# LAN8870_PINOUT.net
KiCad netlist of a schematic drawn in Altium Designer
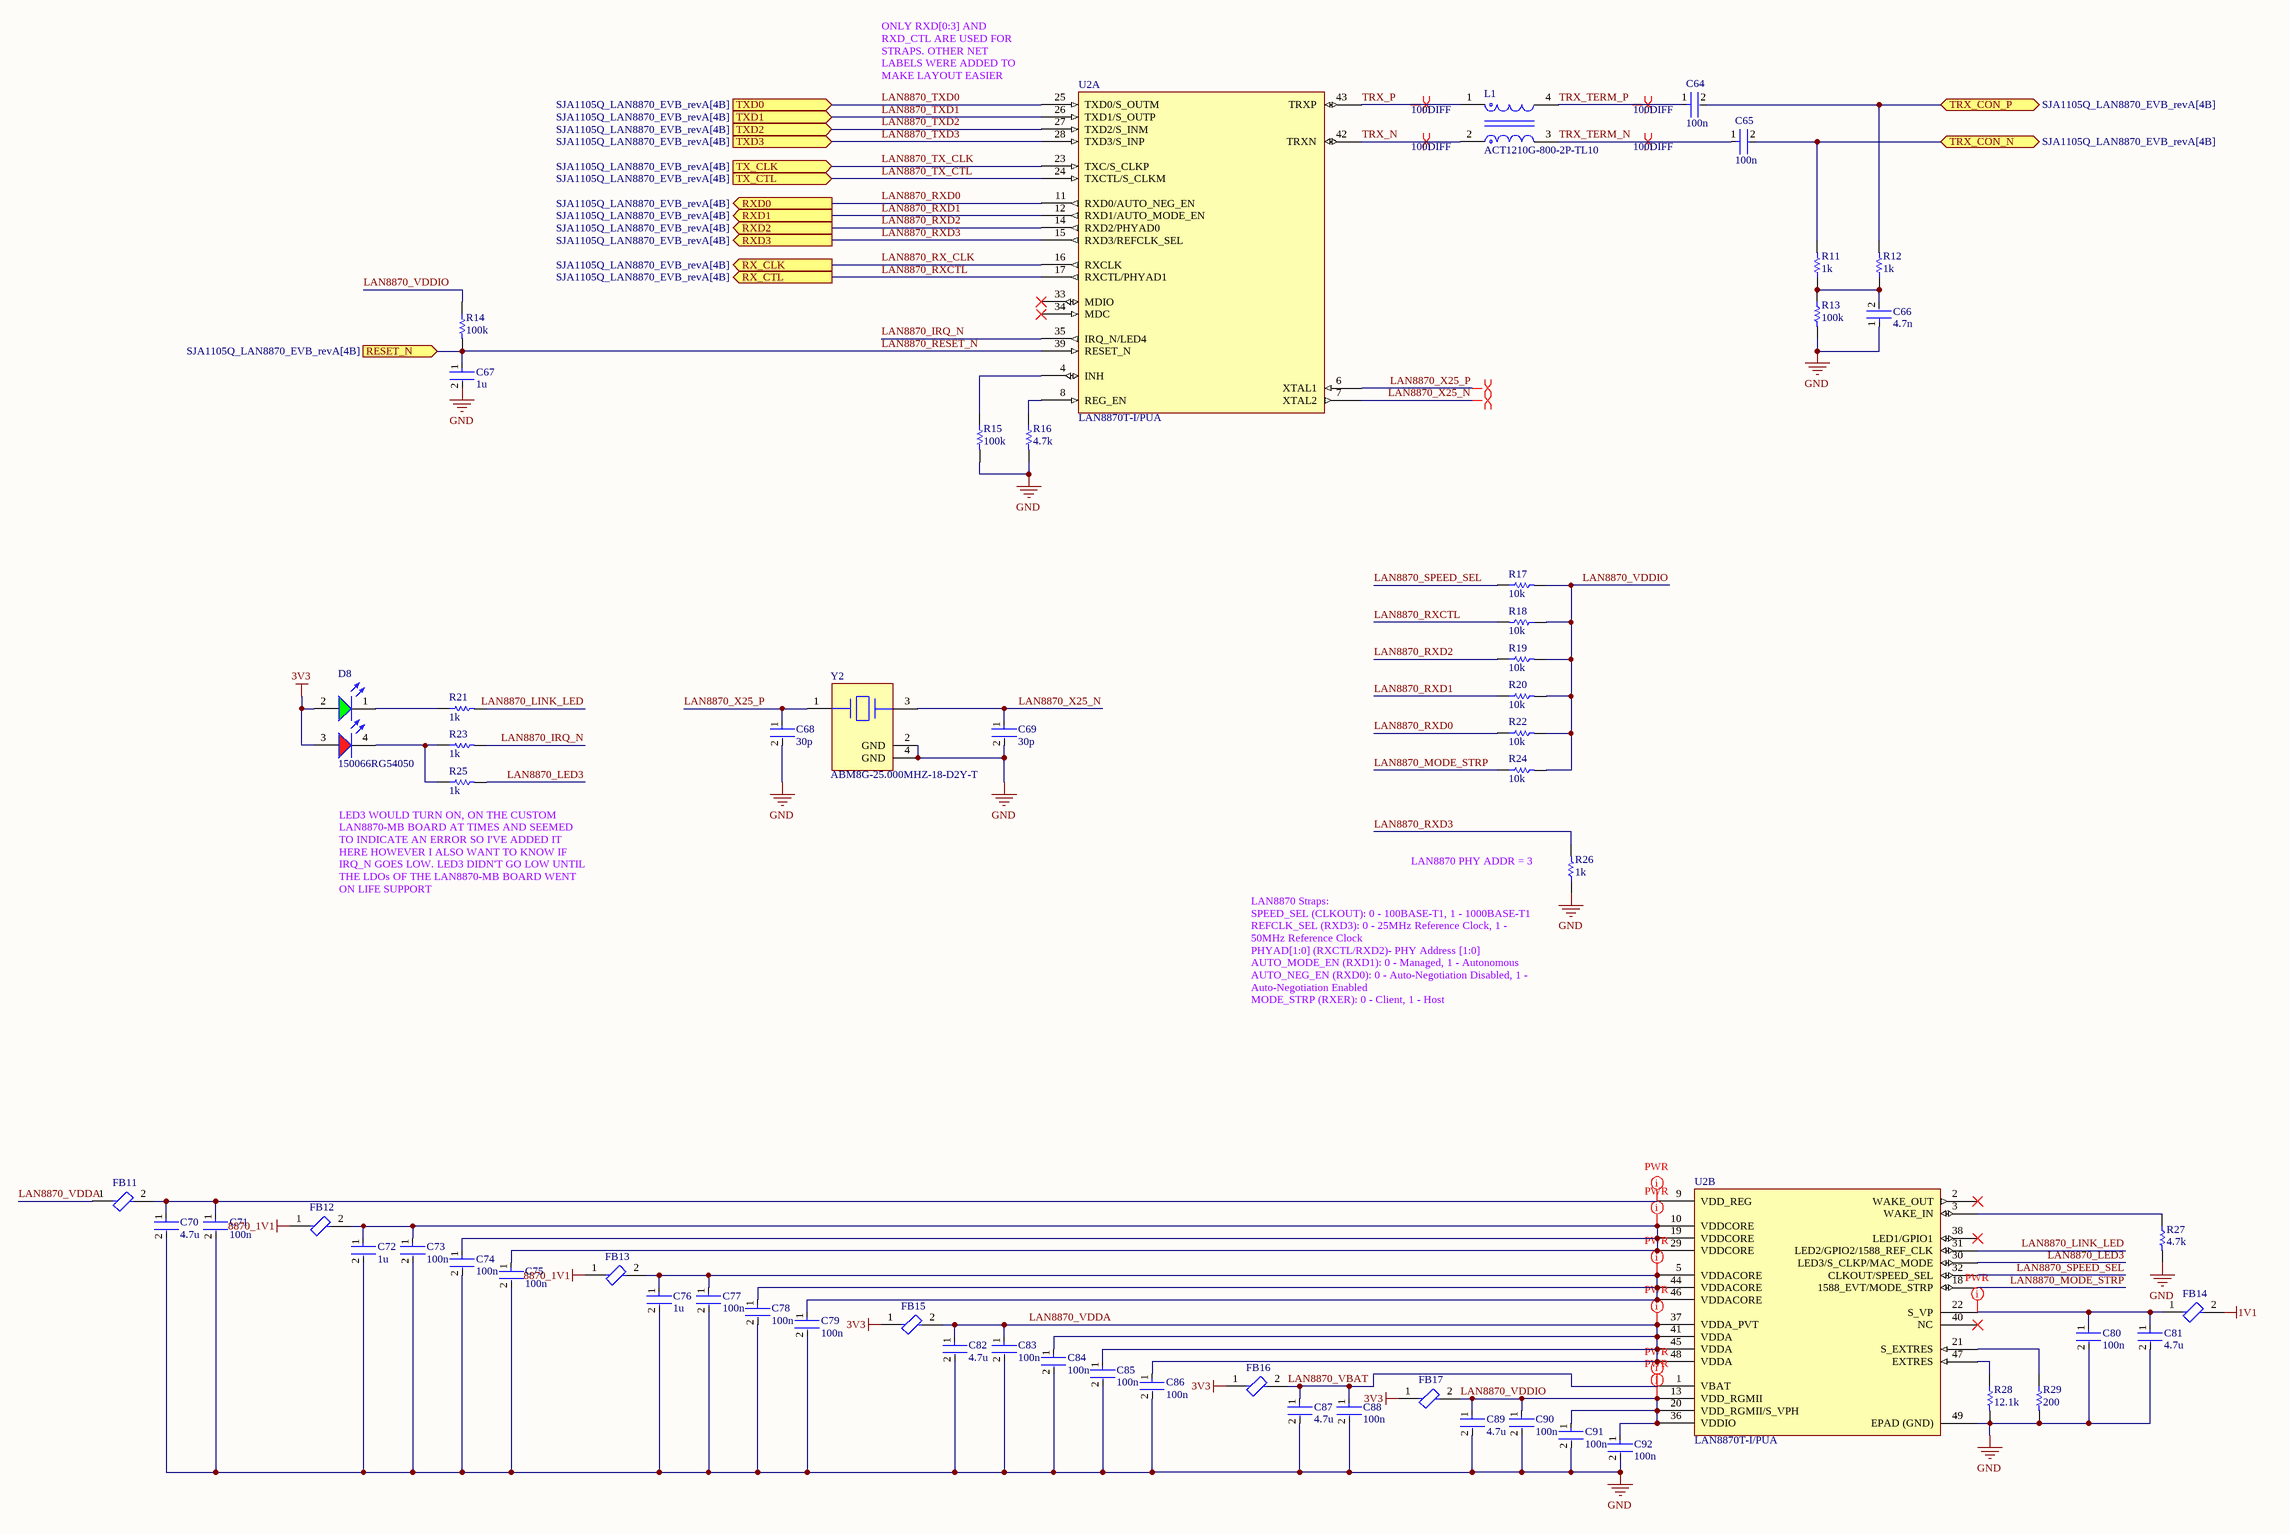
[diagram p0: LAN8870_PINOUT.SchDoc]

(export (version "E")
  (design (tool "Eeschema 10.0.6"))
  (components
    (comp (ref "C64")
      (value "100n")
      (footprint "FP-0402-L_1_0_0_05-W_0_5-IPC_A")
      (description "LARGE PADS, 0402 CAP, CHANGE COMMENT TO MATCH REAL P/N")
      (libsource (lib "Space Concordia") (part "b4654b650e69147ec39a6b967a45e02"))
    )
    (comp (ref "C65")
      (value "100n")
      (footprint "FP-0402-L_1_0_0_05-W_0_5-IPC_A")
      (description "LARGE PADS, 0402 CAP, CHANGE COMMENT TO MATCH REAL P/N")
      (libsource (lib "Space Concordia") (part "b4654b650e69147ec39a6b967a45e02"))
    )
    (comp (ref "C66")
      (value "4.7n")
      (footprint "FP-0402-L_1_0_0_05-W_0_5-IPC_A")
      (description "LARGE PADS, 0402 CAP, CHANGE COMMENT TO MATCH REAL P/N")
      (libsource (lib "Space Concordia") (part "b4654b650e69147ec39a6b967a45e02"))
    )
    (comp (ref "C67")
      (value "1u")
      (footprint "FP-0402-L_1_0_0_05-W_0_5-IPC_A")
      (description "LARGE PADS, 0402 CAP, CHANGE COMMENT TO MATCH REAL P/N")
      (libsource (lib "Space Concordia") (part "b4654b650e69147ec39a6b967a45e02"))
    )
    (comp (ref "C68")
      (value "30p")
      (footprint "FP-0402-L_1_0_0_05-W_0_5-IPC_A")
      (description "LARGE PADS, 0402 CAP, CHANGE COMMENT TO MATCH REAL P/N")
      (libsource (lib "Space Concordia") (part "b4654b650e69147ec39a6b967a45e02"))
    )
    (comp (ref "C69")
      (value "30p")
      (footprint "FP-0402-L_1_0_0_05-W_0_5-IPC_A")
      (description "LARGE PADS, 0402 CAP, CHANGE COMMENT TO MATCH REAL P/N")
      (libsource (lib "Space Concordia") (part "b4654b650e69147ec39a6b967a45e02"))
    )
    (comp (ref "C70")
      (value "4.7u")
      (footprint "FP-0402-L_1_0_0_05-W_0_5-IPC_A")
      (description "LARGE PADS, 0402 CAP, CHANGE COMMENT TO MATCH REAL P/N")
      (libsource (lib "Space Concordia") (part "b4654b650e69147ec39a6b967a45e02"))
    )
    (comp (ref "C71")
      (value "100n")
      (footprint "FP-0402-L_1_0_0_05-W_0_5-IPC_A")
      (description "LARGE PADS, 0402 CAP, CHANGE COMMENT TO MATCH REAL P/N")
      (libsource (lib "Space Concordia") (part "b4654b650e69147ec39a6b967a45e02"))
    )
    (comp (ref "C72")
      (value "1u")
      (footprint "FP-0402-L_1_0_0_05-W_0_5-IPC_A")
      (description "LARGE PADS, 0402 CAP, CHANGE COMMENT TO MATCH REAL P/N")
      (libsource (lib "Space Concordia") (part "b4654b650e69147ec39a6b967a45e02"))
    )
    (comp (ref "C73")
      (value "100n")
      (footprint "FP-0402-L_1_0_0_05-W_0_5-IPC_A")
      (description "LARGE PADS, 0402 CAP, CHANGE COMMENT TO MATCH REAL P/N")
      (libsource (lib "Space Concordia") (part "b4654b650e69147ec39a6b967a45e02"))
    )
    (comp (ref "C74")
      (value "100n")
      (footprint "FP-0402-L_1_0_0_05-W_0_5-IPC_A")
      (description "LARGE PADS, 0402 CAP, CHANGE COMMENT TO MATCH REAL P/N")
      (libsource (lib "Space Concordia") (part "b4654b650e69147ec39a6b967a45e02"))
    )
    (comp (ref "C75")
      (value "100n")
      (footprint "FP-0402-L_1_0_0_05-W_0_5-IPC_A")
      (description "LARGE PADS, 0402 CAP, CHANGE COMMENT TO MATCH REAL P/N")
      (libsource (lib "Space Concordia") (part "b4654b650e69147ec39a6b967a45e02"))
    )
    (comp (ref "C76")
      (value "1u")
      (footprint "FP-0402-L_1_0_0_05-W_0_5-IPC_A")
      (description "LARGE PADS, 0402 CAP, CHANGE COMMENT TO MATCH REAL P/N")
      (libsource (lib "Space Concordia") (part "b4654b650e69147ec39a6b967a45e02"))
    )
    (comp (ref "C77")
      (value "100n")
      (footprint "FP-0402-L_1_0_0_05-W_0_5-IPC_A")
      (description "LARGE PADS, 0402 CAP, CHANGE COMMENT TO MATCH REAL P/N")
      (libsource (lib "Space Concordia") (part "b4654b650e69147ec39a6b967a45e02"))
    )
    (comp (ref "C78")
      (value "100n")
      (footprint "FP-0402-L_1_0_0_05-W_0_5-IPC_A")
      (description "LARGE PADS, 0402 CAP, CHANGE COMMENT TO MATCH REAL P/N")
      (libsource (lib "Space Concordia") (part "b4654b650e69147ec39a6b967a45e02"))
    )
    (comp (ref "C79")
      (value "100n")
      (footprint "FP-0402-L_1_0_0_05-W_0_5-IPC_A")
      (description "LARGE PADS, 0402 CAP, CHANGE COMMENT TO MATCH REAL P/N")
      (libsource (lib "Space Concordia") (part "b4654b650e69147ec39a6b967a45e02"))
    )
    (comp (ref "C80")
      (value "100n")
      (footprint "FP-0402-L_1_0_0_05-W_0_5-IPC_A")
      (description "LARGE PADS, 0402 CAP, CHANGE COMMENT TO MATCH REAL P/N")
      (libsource (lib "Space Concordia") (part "b4654b650e69147ec39a6b967a45e02"))
    )
    (comp (ref "C81")
      (value "4.7u")
      (footprint "FP-0402-L_1_0_0_05-W_0_5-IPC_A")
      (description "LARGE PADS, 0402 CAP, CHANGE COMMENT TO MATCH REAL P/N")
      (libsource (lib "Space Concordia") (part "b4654b650e69147ec39a6b967a45e02"))
    )
    (comp (ref "C82")
      (value "4.7u")
      (footprint "FP-0402-L_1_0_0_05-W_0_5-IPC_A")
      (description "LARGE PADS, 0402 CAP, CHANGE COMMENT TO MATCH REAL P/N")
      (libsource (lib "Space Concordia") (part "b4654b650e69147ec39a6b967a45e02"))
    )
    (comp (ref "C83")
      (value "100n")
      (footprint "FP-0402-L_1_0_0_05-W_0_5-IPC_A")
      (description "LARGE PADS, 0402 CAP, CHANGE COMMENT TO MATCH REAL P/N")
      (libsource (lib "Space Concordia") (part "b4654b650e69147ec39a6b967a45e02"))
    )
    (comp (ref "C84")
      (value "100n")
      (footprint "FP-0402-L_1_0_0_05-W_0_5-IPC_A")
      (description "LARGE PADS, 0402 CAP, CHANGE COMMENT TO MATCH REAL P/N")
      (libsource (lib "Space Concordia") (part "b4654b650e69147ec39a6b967a45e02"))
    )
    (comp (ref "C85")
      (value "100n")
      (footprint "FP-0402-L_1_0_0_05-W_0_5-IPC_A")
      (description "LARGE PADS, 0402 CAP, CHANGE COMMENT TO MATCH REAL P/N")
      (libsource (lib "Space Concordia") (part "b4654b650e69147ec39a6b967a45e02"))
    )
    (comp (ref "C86")
      (value "100n")
      (footprint "FP-0402-L_1_0_0_05-W_0_5-IPC_A")
      (description "LARGE PADS, 0402 CAP, CHANGE COMMENT TO MATCH REAL P/N")
      (libsource (lib "Space Concordia") (part "b4654b650e69147ec39a6b967a45e02"))
    )
    (comp (ref "C87")
      (value "4.7u")
      (footprint "FP-0402-L_1_0_0_05-W_0_5-IPC_A")
      (description "LARGE PADS, 0402 CAP, CHANGE COMMENT TO MATCH REAL P/N")
      (libsource (lib "Space Concordia") (part "b4654b650e69147ec39a6b967a45e02"))
    )
    (comp (ref "C88")
      (value "100n")
      (footprint "FP-0402-L_1_0_0_05-W_0_5-IPC_A")
      (description "LARGE PADS, 0402 CAP, CHANGE COMMENT TO MATCH REAL P/N")
      (libsource (lib "Space Concordia") (part "b4654b650e69147ec39a6b967a45e02"))
    )
    (comp (ref "C89")
      (value "4.7u")
      (footprint "FP-0402-L_1_0_0_05-W_0_5-IPC_A")
      (description "LARGE PADS, 0402 CAP, CHANGE COMMENT TO MATCH REAL P/N")
      (libsource (lib "Space Concordia") (part "b4654b650e69147ec39a6b967a45e02"))
    )
    (comp (ref "C90")
      (value "100n")
      (footprint "FP-0402-L_1_0_0_05-W_0_5-IPC_A")
      (description "LARGE PADS, 0402 CAP, CHANGE COMMENT TO MATCH REAL P/N")
      (libsource (lib "Space Concordia") (part "b4654b650e69147ec39a6b967a45e02"))
    )
    (comp (ref "C91")
      (value "100n")
      (footprint "FP-0402-L_1_0_0_05-W_0_5-IPC_A")
      (description "LARGE PADS, 0402 CAP, CHANGE COMMENT TO MATCH REAL P/N")
      (libsource (lib "Space Concordia") (part "b4654b650e69147ec39a6b967a45e02"))
    )
    (comp (ref "C92")
      (value "100n")
      (footprint "FP-0402-L_1_0_0_05-W_0_5-IPC_A")
      (description "LARGE PADS, 0402 CAP, CHANGE COMMENT TO MATCH REAL P/N")
      (libsource (lib "Space Concordia") (part "b4654b650e69147ec39a6b967a45e02"))
    )
    (comp (ref "D8")
      (value "150066RG54050")
      (footprint "WL-SBCD_0606")
      (description "Led, Red/Grn, 180Mcd/230Mcd, 624Nm/525Nm Rohs Compliant: Yes")
      (fields (field (name "SOURCE") "rgled.SchLib"))
      (libsource (lib "Space Concordia") (part "CMP-004-00034-2"))
    )
    (comp (ref "FB11")
      (value "BLM18KG331SH1D")
      (footprint "FP-BLM18-0_15-t0_8-IPC_B")
      (description "Chip Ferrite Bead, 0603, 330Ω @ 100MHz, 0.08Ω, 25%, 1.7A")
      (libsource (lib "Altium Content Vault") (part "5f30dd21d616792df468990f7003faa"))
    )
    (comp (ref "FB12")
      (value "BLM18KG331SH1D")
      (footprint "FP-BLM18-0_15-t0_8-IPC_B")
      (description "Chip Ferrite Bead, 0603, 330Ω @ 100MHz, 0.08Ω, 25%, 1.7A")
      (libsource (lib "Altium Content Vault") (part "5f30dd21d616792df468990f7003faa"))
    )
    (comp (ref "FB13")
      (value "BLM18KG331SH1D")
      (footprint "FP-BLM18-0_15-t0_8-IPC_B")
      (description "Chip Ferrite Bead, 0603, 330Ω @ 100MHz, 0.08Ω, 25%, 1.7A")
      (libsource (lib "Altium Content Vault") (part "5f30dd21d616792df468990f7003faa"))
    )
    (comp (ref "FB14")
      (value "BLM18KG331SH1D")
      (footprint "FP-BLM18-0_15-t0_8-IPC_B")
      (description "Chip Ferrite Bead, 0603, 330Ω @ 100MHz, 0.08Ω, 25%, 1.7A")
      (libsource (lib "Altium Content Vault") (part "5f30dd21d616792df468990f7003faa"))
    )
    (comp (ref "FB15")
      (value "BLM18KG331SH1D")
      (footprint "FP-BLM18-0_15-t0_8-IPC_B")
      (description "Chip Ferrite Bead, 0603, 330Ω @ 100MHz, 0.08Ω, 25%, 1.7A")
      (libsource (lib "Altium Content Vault") (part "5f30dd21d616792df468990f7003faa"))
    )
    (comp (ref "FB16")
      (value "BLM18KG331SH1D")
      (footprint "FP-BLM18-0_15-t0_8-IPC_B")
      (description "Chip Ferrite Bead, 0603, 330Ω @ 100MHz, 0.08Ω, 25%, 1.7A")
      (libsource (lib "Altium Content Vault") (part "5f30dd21d616792df468990f7003faa"))
    )
    (comp (ref "FB17")
      (value "BLM18KG331SH1D")
      (footprint "FP-BLM18-0_15-t0_8-IPC_B")
      (description "Chip Ferrite Bead, 0603, 330Ω @ 100MHz, 0.08Ω, 25%, 1.7A")
      (libsource (lib "Altium Content Vault") (part "5f30dd21d616792df468990f7003faa"))
    )
    (comp (ref "L1")
      (value "ACT1210G-800-2P-TL10")
      (footprint "FP-ACT1210G-800-2P-TL10-MFG")
      (description "CMC 80UH 70MA 2LN 3.8KOHM SMD")
      (libsource (lib "Altium Content Vault") (part "b4b74a627ea9af473eaab86227aab92"))
    )
    (comp (ref "R11")
      (value "1k")
      (footprint "R0603B")
      (description "Resistor")
      (libsource (lib "Space Concordia") (part "Resistor"))
    )
    (comp (ref "R12")
      (value "1k")
      (footprint "R0603B")
      (description "Resistor")
      (libsource (lib "Space Concordia") (part "Resistor"))
    )
    (comp (ref "R13")
      (value "100k")
      (footprint "R0603B")
      (description "Resistor")
      (libsource (lib "Space Concordia") (part "Resistor"))
    )
    (comp (ref "R14")
      (value "100k")
      (footprint "R0603B")
      (description "Resistor")
      (libsource (lib "Space Concordia") (part "Resistor"))
    )
    (comp (ref "R15")
      (value "100k")
      (footprint "R0603B")
      (description "Resistor")
      (libsource (lib "Space Concordia") (part "Resistor"))
    )
    (comp (ref "R16")
      (value "4.7k")
      (footprint "R0603B")
      (description "Resistor")
      (libsource (lib "Space Concordia") (part "Resistor"))
    )
    (comp (ref "R17")
      (value "10k")
      (footprint "R0603B")
      (description "Resistor")
      (libsource (lib "Space Concordia") (part "Resistor"))
    )
    (comp (ref "R18")
      (value "10k")
      (footprint "R0603B")
      (description "Resistor")
      (libsource (lib "Space Concordia") (part "Resistor"))
    )
    (comp (ref "R19")
      (value "10k")
      (footprint "R0603B")
      (description "Resistor")
      (libsource (lib "Space Concordia") (part "Resistor"))
    )
    (comp (ref "R20")
      (value "10k")
      (footprint "R0603B")
      (description "Resistor")
      (libsource (lib "Space Concordia") (part "Resistor"))
    )
    (comp (ref "R21")
      (value "1k")
      (footprint "R0603B")
      (description "Resistor")
      (libsource (lib "Space Concordia") (part "Resistor"))
    )
    (comp (ref "R22")
      (value "10k")
      (footprint "R0603B")
      (description "Resistor")
      (libsource (lib "Space Concordia") (part "Resistor"))
    )
    (comp (ref "R23")
      (value "1k")
      (footprint "R0603B")
      (description "Resistor")
      (libsource (lib "Space Concordia") (part "Resistor"))
    )
    (comp (ref "R24")
      (value "10k")
      (footprint "R0603B")
      (description "Resistor")
      (libsource (lib "Space Concordia") (part "Resistor"))
    )
    (comp (ref "R25")
      (value "1k")
      (footprint "R0603B")
      (description "Resistor")
      (libsource (lib "Space Concordia") (part "Resistor"))
    )
    (comp (ref "R26")
      (value "1k")
      (footprint "R0603B")
      (description "Resistor")
      (libsource (lib "Space Concordia") (part "Resistor"))
    )
    (comp (ref "R27")
      (value "4.7k")
      (footprint "R0603B")
      (description "Resistor")
      (libsource (lib "Space Concordia") (part "Resistor"))
    )
    (comp (ref "R28")
      (value "12.1k")
      (footprint "R0603B")
      (description "Resistor")
      (libsource (lib "Space Concordia") (part "Resistor"))
    )
    (comp (ref "R29")
      (value "200")
      (footprint "R0603B")
      (description "Resistor")
      (libsource (lib "Space Concordia") (part "Resistor"))
    )
    (comp (ref "U2")
      (value "LAN8870T-I/PUA")
      (footprint "QFN50P700X700X100_HS-49N")
      (description "100/1000BASE-T1 Rgmii/sgmii Phy")
      (libsource (lib "Space Concordia") (part "LAN8870T-I_PUA"))
    )
    (comp (ref "Y2")
      (value "ABM8G-25.000MHZ-18-D2Y-T")
      (footprint "FP-ABM8G-MFG")
      (description "Crystal 25MHz ±20ppm (Tol) ±30ppm (Stability) 18pF FUND 60Ω 4-Pin SMD T/R")
      (fields (field (name "TOLERANCE") "20ppm"))
      (libsource (lib "Altium Content Vault") (part "48e526d86b7f2615d98721063c72f49"))
    )
  )
  (nets
    (net (code "1") (name "/LAN8870_IRQ_N") (class "Default")
      (node (ref "R23") (pin "2") (pinfunction "2_2") (pintype "passive"))
      (node (ref "U2") (pin "35") (pinfunction "IRQ_N/LED4_35") (pintype "output"))
    )
    (net (code "2") (name "/LAN8870_LED3") (class "Default")
      (node (ref "R25") (pin "2") (pinfunction "2_2") (pintype "passive"))
      (node (ref "U2") (pin "30") (pinfunction "LED3/S_CLKP/MAC_MODE_30") (pintype "bidirectional"))
    )
    (net (code "3") (name "/LAN8870_LINK_LED") (class "Default")
      (node (ref "R21") (pin "2") (pinfunction "2_2") (pintype "passive"))
      (node (ref "U2") (pin "31") (pinfunction "LED2/GPIO2/1588_REF_CLK_31") (pintype "bidirectional"))
    )
    (net (code "4") (name "/LAN8870_MODE_STRP") (class "Default")
      (node (ref "R24") (pin "1") (pinfunction "1_1") (pintype "passive"))
      (node (ref "U2") (pin "18") (pinfunction "1588_EVT/MODE_STRP_18") (pintype "bidirectional"))
    )
    (net (code "5") (name "/LAN8870_RESET_N") (class "Default")
      (node (ref "C67") (pin "1") (pinfunction "1_1") (pintype "passive"))
      (node (ref "R14") (pin "2") (pinfunction "2_2") (pintype "passive"))
      (node (ref "U2") (pin "39") (pinfunction "RESET_N_39") (pintype "input"))
    )
    (net (code "6") (name "/LAN8870_RXCTL") (class "Default")
      (node (ref "R18") (pin "2") (pinfunction "2_2") (pintype "passive"))
      (node (ref "U2") (pin "17") (pinfunction "RXCTL/PHYAD1_17") (pintype "output"))
    )
    (net (code "7") (name "/LAN8870_RXD0") (class "Default")
      (node (ref "R22") (pin "1") (pinfunction "1_1") (pintype "passive"))
      (node (ref "U2") (pin "11") (pinfunction "RXD0/AUTO_NEG_EN_11") (pintype "output"))
    )
    (net (code "8") (name "/LAN8870_RXD1") (class "Default")
      (node (ref "R20") (pin "1") (pinfunction "1_1") (pintype "passive"))
      (node (ref "U2") (pin "12") (pinfunction "RXD1/AUTO_MODE_EN_12") (pintype "output"))
    )
    (net (code "9") (name "/LAN8870_RXD2") (class "Default")
      (node (ref "R19") (pin "1") (pinfunction "1_1") (pintype "passive"))
      (node (ref "U2") (pin "14") (pinfunction "RXD2/PHYAD0_14") (pintype "output"))
    )
    (net (code "10") (name "/LAN8870_RXD3") (class "Default")
      (node (ref "R26") (pin "2") (pinfunction "2_2") (pintype "passive"))
      (node (ref "U2") (pin "15") (pinfunction "RXD3/REFCLK_SEL_15") (pintype "output"))
    )
    (net (code "11") (name "/LAN8870_RX_CLK") (class "Default")
      (node (ref "U2") (pin "16") (pinfunction "RXCLK_16") (pintype "output"))
    )
    (net (code "12") (name "/LAN8870_SPEED_SEL") (class "Default")
      (node (ref "R17") (pin "1") (pinfunction "1_1") (pintype "passive"))
      (node (ref "U2") (pin "32") (pinfunction "CLKOUT/SPEED_SEL_32") (pintype "bidirectional"))
    )
    (net (code "13") (name "/LAN8870_TXD0") (class "Default")
      (node (ref "U2") (pin "25") (pinfunction "TXD0/S_OUTM_25") (pintype "input"))
    )
    (net (code "14") (name "/LAN8870_TXD1") (class "Default")
      (node (ref "U2") (pin "26") (pinfunction "TXD1/S_OUTP_26") (pintype "input"))
    )
    (net (code "15") (name "/LAN8870_TXD2") (class "Default")
      (node (ref "U2") (pin "27") (pinfunction "TXD2/S_INM_27") (pintype "input"))
    )
    (net (code "16") (name "/LAN8870_TXD3") (class "Default")
      (node (ref "U2") (pin "28") (pinfunction "TXD3/S_INP_28") (pintype "input"))
    )
    (net (code "17") (name "/LAN8870_TX_CLK") (class "Default")
      (node (ref "U2") (pin "23") (pinfunction "TXC/S_CLKP_23") (pintype "input"))
    )
    (net (code "18") (name "/LAN8870_TX_CTL") (class "Default")
      (node (ref "U2") (pin "24") (pinfunction "TXCTL/S_CLKM_24") (pintype "input"))
    )
    (net (code "19") (name "/LAN8870_VBAT") (class "Default")
      (node (ref "C87") (pin "1") (pinfunction "1_1") (pintype "passive"))
      (node (ref "C88") (pin "1") (pinfunction "1_1") (pintype "passive"))
      (node (ref "FB16") (pin "2") (pinfunction "2_2") (pintype "passive"))
      (node (ref "U2") (pin "1") (pinfunction "VBAT_1") (pintype "power_in"))
    )
    (net (code "20") (name "/LAN8870_VDDA") (class "Default")
      (node (ref "C82") (pin "1") (pinfunction "1_1") (pintype "passive"))
      (node (ref "C83") (pin "1") (pinfunction "1_1") (pintype "passive"))
      (node (ref "C84") (pin "1") (pinfunction "1_1") (pintype "passive"))
      (node (ref "C85") (pin "1") (pinfunction "1_1") (pintype "passive"))
      (node (ref "C86") (pin "1") (pinfunction "1_1") (pintype "passive"))
      (node (ref "FB11") (pin "1") (pinfunction "1_1") (pintype "passive"))
      (node (ref "FB15") (pin "2") (pinfunction "2_2") (pintype "passive"))
      (node (ref "U2") (pin "37") (pinfunction "VDDA_PVT_37") (pintype "power_in"))
      (node (ref "U2") (pin "41") (pinfunction "VDDA_41") (pintype "power_in"))
      (node (ref "U2") (pin "45") (pinfunction "VDDA_45") (pintype "power_in"))
      (node (ref "U2") (pin "48") (pinfunction "VDDA_48") (pintype "power_in"))
    )
    (net (code "21") (name "/LAN8870_VDDIO") (class "Default")
      (node (ref "C89") (pin "1") (pinfunction "1_1") (pintype "passive"))
      (node (ref "C90") (pin "1") (pinfunction "1_1") (pintype "passive"))
      (node (ref "C91") (pin "1") (pinfunction "1_1") (pintype "passive"))
      (node (ref "C92") (pin "1") (pinfunction "1_1") (pintype "passive"))
      (node (ref "FB17") (pin "2") (pinfunction "2_2") (pintype "passive"))
      (node (ref "R14") (pin "1") (pinfunction "1_1") (pintype "passive"))
      (node (ref "R17") (pin "2") (pinfunction "2_2") (pintype "passive"))
      (node (ref "R18") (pin "1") (pinfunction "1_1") (pintype "passive"))
      (node (ref "R19") (pin "2") (pinfunction "2_2") (pintype "passive"))
      (node (ref "R20") (pin "2") (pinfunction "2_2") (pintype "passive"))
      (node (ref "R22") (pin "2") (pinfunction "2_2") (pintype "passive"))
      (node (ref "R24") (pin "2") (pinfunction "2_2") (pintype "passive"))
      (node (ref "U2") (pin "13") (pinfunction "VDD_RGMII_13") (pintype "power_in"))
      (node (ref "U2") (pin "20") (pinfunction "VDD_RGMII/S_VPH_20") (pintype "power_in"))
      (node (ref "U2") (pin "36") (pinfunction "VDDIO_36") (pintype "power_in"))
    )
    (net (code "22") (name "/LAN8870_X25_N") (class "Default")
      (node (ref "C69") (pin "1") (pinfunction "1_1") (pintype "passive"))
      (node (ref "U2") (pin "7") (pinfunction "XTAL2_7") (pintype "output"))
      (node (ref "Y2") (pin "3") (pinfunction "3_3") (pintype "passive"))
    )
    (net (code "23") (name "/LAN8870_X25_P") (class "Default")
      (node (ref "C68") (pin "1") (pinfunction "1_1") (pintype "passive"))
      (node (ref "U2") (pin "6") (pinfunction "XTAL1_6") (pintype "input"))
      (node (ref "Y2") (pin "1") (pinfunction "1_1") (pintype "passive"))
    )
    (net (code "24") (name "/TRX_CON_N") (class "Default")
      (node (ref "C65") (pin "2") (pinfunction "2_2") (pintype "passive"))
      (node (ref "R11") (pin "2") (pinfunction "2_2") (pintype "passive"))
    )
    (net (code "25") (name "/TRX_CON_P") (class "Default")
      (node (ref "C64") (pin "2") (pinfunction "2_2") (pintype "passive"))
      (node (ref "R12") (pin "2") (pinfunction "2_2") (pintype "passive"))
    )
    (net (code "26") (name "/TRX_N") (class "Default")
      (node (ref "L1") (pin "2") (pinfunction "2_2") (pintype "passive"))
      (node (ref "U2") (pin "42") (pinfunction "TRXN_42") (pintype "bidirectional"))
    )
    (net (code "27") (name "/TRX_P") (class "Default")
      (node (ref "L1") (pin "1") (pinfunction "1_1") (pintype "passive"))
      (node (ref "U2") (pin "43") (pinfunction "TRXP_43") (pintype "bidirectional"))
    )
    (net (code "28") (name "/TRX_TERM_N") (class "Default")
      (node (ref "C65") (pin "1") (pinfunction "1_1") (pintype "passive"))
      (node (ref "L1") (pin "3") (pinfunction "3_3") (pintype "passive"))
    )
    (net (code "29") (name "/TRX_TERM_P") (class "Default")
      (node (ref "C64") (pin "1") (pinfunction "1_1") (pintype "passive"))
      (node (ref "L1") (pin "4") (pinfunction "4_4") (pintype "passive"))
    )
    (net (code "30") (name "1V1") (class "Default")
      (node (ref "FB14") (pin "2") (pinfunction "2_2") (pintype "passive"))
    )
    (net (code "31") (name "3V3") (class "Default")
      (node (ref "D8") (pin "2") (pinfunction "A_2") (pintype "passive"))
      (node (ref "D8") (pin "3") (pinfunction "A_3") (pintype "passive"))
      (node (ref "FB15") (pin "1") (pinfunction "1_1") (pintype "passive"))
      (node (ref "FB16") (pin "1") (pinfunction "1_1") (pintype "passive"))
      (node (ref "FB17") (pin "1") (pinfunction "1_1") (pintype "passive"))
    )
    (net (code "32") (name "8870_1V1") (class "Default")
      (node (ref "FB12") (pin "1") (pinfunction "1_1") (pintype "passive"))
      (node (ref "FB13") (pin "1") (pinfunction "1_1") (pintype "passive"))
    )
    (net (code "33") (name "GND") (class "Default")
      (node (ref "C66") (pin "1") (pinfunction "1_1") (pintype "passive"))
      (node (ref "C67") (pin "2") (pinfunction "2_2") (pintype "passive"))
      (node (ref "C68") (pin "2") (pinfunction "2_2") (pintype "passive"))
      (node (ref "C69") (pin "2") (pinfunction "2_2") (pintype "passive"))
      (node (ref "C70") (pin "2") (pinfunction "2_2") (pintype "passive"))
      (node (ref "C71") (pin "2") (pinfunction "2_2") (pintype "passive"))
      (node (ref "C72") (pin "2") (pinfunction "2_2") (pintype "passive"))
      (node (ref "C73") (pin "2") (pinfunction "2_2") (pintype "passive"))
      (node (ref "C74") (pin "2") (pinfunction "2_2") (pintype "passive"))
      (node (ref "C75") (pin "2") (pinfunction "2_2") (pintype "passive"))
      (node (ref "C76") (pin "2") (pinfunction "2_2") (pintype "passive"))
      (node (ref "C77") (pin "2") (pinfunction "2_2") (pintype "passive"))
      (node (ref "C78") (pin "2") (pinfunction "2_2") (pintype "passive"))
      (node (ref "C79") (pin "2") (pinfunction "2_2") (pintype "passive"))
      (node (ref "C80") (pin "2") (pinfunction "2_2") (pintype "passive"))
      (node (ref "C81") (pin "2") (pinfunction "2_2") (pintype "passive"))
      (node (ref "C82") (pin "2") (pinfunction "2_2") (pintype "passive"))
      (node (ref "C83") (pin "2") (pinfunction "2_2") (pintype "passive"))
      (node (ref "C84") (pin "2") (pinfunction "2_2") (pintype "passive"))
      (node (ref "C85") (pin "2") (pinfunction "2_2") (pintype "passive"))
      (node (ref "C86") (pin "2") (pinfunction "2_2") (pintype "passive"))
      (node (ref "C87") (pin "2") (pinfunction "2_2") (pintype "passive"))
      (node (ref "C88") (pin "2") (pinfunction "2_2") (pintype "passive"))
      (node (ref "C89") (pin "2") (pinfunction "2_2") (pintype "passive"))
      (node (ref "C90") (pin "2") (pinfunction "2_2") (pintype "passive"))
      (node (ref "C91") (pin "2") (pinfunction "2_2") (pintype "passive"))
      (node (ref "C92") (pin "2") (pinfunction "2_2") (pintype "passive"))
      (node (ref "R13") (pin "2") (pinfunction "2_2") (pintype "passive"))
      (node (ref "R15") (pin "2") (pinfunction "2_2") (pintype "passive"))
      (node (ref "R16") (pin "2") (pinfunction "2_2") (pintype "passive"))
      (node (ref "R26") (pin "1") (pinfunction "1_1") (pintype "passive"))
      (node (ref "R27") (pin "2") (pinfunction "2_2") (pintype "passive"))
      (node (ref "R28") (pin "2") (pinfunction "2_2") (pintype "passive"))
      (node (ref "R29") (pin "2") (pinfunction "2_2") (pintype "passive"))
      (node (ref "U2") (pin "49") (pinfunction "EPAD_(GND)_49") (pintype "power_in"))
      (node (ref "Y2") (pin "2") (pinfunction "GND_2") (pintype "power_in"))
      (node (ref "Y2") (pin "4") (pinfunction "GND_4") (pintype "power_in"))
    )
    (net (code "34") (name "Net-(C66-Pad2)") (class "Default")
      (node (ref "C66") (pin "2") (pinfunction "2_2") (pintype "passive"))
      (node (ref "R11") (pin "1") (pinfunction "1_1") (pintype "passive"))
      (node (ref "R12") (pin "1") (pinfunction "1_1") (pintype "passive"))
      (node (ref "R13") (pin "1") (pinfunction "1_1") (pintype "passive"))
    )
    (net (code "35") (name "Net-(C72-Pad1)") (class "Default")
      (node (ref "C72") (pin "1") (pinfunction "1_1") (pintype "passive"))
      (node (ref "C73") (pin "1") (pinfunction "1_1") (pintype "passive"))
      (node (ref "C74") (pin "1") (pinfunction "1_1") (pintype "passive"))
      (node (ref "C75") (pin "1") (pinfunction "1_1") (pintype "passive"))
      (node (ref "FB12") (pin "2") (pinfunction "2_2") (pintype "passive"))
      (node (ref "U2") (pin "10") (pinfunction "VDDCORE_10") (pintype "power_in"))
      (node (ref "U2") (pin "19") (pinfunction "VDDCORE_19") (pintype "power_in"))
      (node (ref "U2") (pin "29") (pinfunction "VDDCORE_29") (pintype "power_in"))
    )
    (net (code "36") (name "Net-(C76-Pad1)") (class "Default")
      (node (ref "C76") (pin "1") (pinfunction "1_1") (pintype "passive"))
      (node (ref "C77") (pin "1") (pinfunction "1_1") (pintype "passive"))
      (node (ref "C78") (pin "1") (pinfunction "1_1") (pintype "passive"))
      (node (ref "C79") (pin "1") (pinfunction "1_1") (pintype "passive"))
      (node (ref "FB13") (pin "2") (pinfunction "2_2") (pintype "passive"))
      (node (ref "U2") (pin "44") (pinfunction "VDDACORE_44") (pintype "power_in"))
      (node (ref "U2") (pin "46") (pinfunction "VDDACORE_46") (pintype "power_in"))
      (node (ref "U2") (pin "5") (pinfunction "VDDACORE_5") (pintype "power_in"))
    )
    (net (code "37") (name "Net-(D8-K-Pad1)") (class "Default")
      (node (ref "D8") (pin "1") (pinfunction "K_1") (pintype "passive"))
      (node (ref "R21") (pin "1") (pinfunction "1_1") (pintype "passive"))
    )
    (net (code "38") (name "Net-(D8-K-Pad4)") (class "Default")
      (node (ref "D8") (pin "4") (pinfunction "K_4") (pintype "passive"))
      (node (ref "R23") (pin "1") (pinfunction "1_1") (pintype "passive"))
      (node (ref "R25") (pin "1") (pinfunction "1_1") (pintype "passive"))
    )
    (net (code "39") (name "Net-(U2A-INH)") (class "Default")
      (node (ref "R15") (pin "1") (pinfunction "1_1") (pintype "passive"))
      (node (ref "U2") (pin "4") (pinfunction "INH_4") (pintype "bidirectional"))
    )
    (net (code "40") (name "Net-(U2A-REG_EN)") (class "Default")
      (node (ref "R16") (pin "1") (pinfunction "1_1") (pintype "passive"))
      (node (ref "U2") (pin "8") (pinfunction "REG_EN_8") (pintype "input"))
    )
    (net (code "41") (name "Net-(U2B-EXTRES)") (class "Default")
      (node (ref "R28") (pin "1") (pinfunction "1_1") (pintype "passive"))
      (node (ref "U2") (pin "47") (pinfunction "EXTRES_47") (pintype "input"))
    )
    (net (code "42") (name "Net-(U2B-S_EXTRES)") (class "Default")
      (node (ref "R29") (pin "1") (pinfunction "1_1") (pintype "passive"))
      (node (ref "U2") (pin "21") (pinfunction "S_EXTRES_21") (pintype "input"))
    )
    (net (code "43") (name "Net-(U2B-S_VP)") (class "Default")
      (node (ref "C80") (pin "1") (pinfunction "1_1") (pintype "passive"))
      (node (ref "C81") (pin "1") (pinfunction "1_1") (pintype "passive"))
      (node (ref "FB14") (pin "1") (pinfunction "1_1") (pintype "passive"))
      (node (ref "U2") (pin "22") (pinfunction "S_VP_22") (pintype "passive"))
    )
    (net (code "44") (name "Net-(U2B-VDD_REG)") (class "Default")
      (node (ref "C70") (pin "1") (pinfunction "1_1") (pintype "passive"))
      (node (ref "C71") (pin "1") (pinfunction "1_1") (pintype "passive"))
      (node (ref "FB11") (pin "2") (pinfunction "2_2") (pintype "passive"))
      (node (ref "U2") (pin "9") (pinfunction "VDD_REG_9") (pintype "power_in"))
    )
    (net (code "45") (name "Net-(U2B-WAKE_IN)") (class "Default")
      (node (ref "R27") (pin "1") (pinfunction "1_1") (pintype "passive"))
      (node (ref "U2") (pin "3") (pinfunction "WAKE_IN_3") (pintype "bidirectional"))
    )
    (net (code "46") (name "unconnected-(U2A-MDC-Pad34)") (class "Default")
      (node (ref "U2") (pin "34") (pinfunction "MDC_34") (pintype "input+no_connect"))
    )
    (net (code "47") (name "unconnected-(U2A-MDIO-Pad33)") (class "Default")
      (node (ref "U2") (pin "33") (pinfunction "MDIO_33") (pintype "bidirectional+no_connect"))
    )
    (net (code "48") (name "unconnected-(U2B-LED1{slash}GPIO1-Pad38)") (class "Default")
      (node (ref "U2") (pin "38") (pinfunction "LED1/GPIO1_38") (pintype "bidirectional+no_connect"))
    )
    (net (code "49") (name "unconnected-(U2B-NC-Pad40)") (class "Default")
      (node (ref "U2") (pin "40") (pinfunction "NC_40") (pintype "passive+no_connect"))
    )
    (net (code "50") (name "unconnected-(U2B-WAKE_OUT-Pad2)") (class "Default")
      (node (ref "U2") (pin "2") (pinfunction "WAKE_OUT_2") (pintype "output+no_connect"))
    )
  )
)
